# Circuit.net
KiCad netlist of a schematic drawn in EAGLE
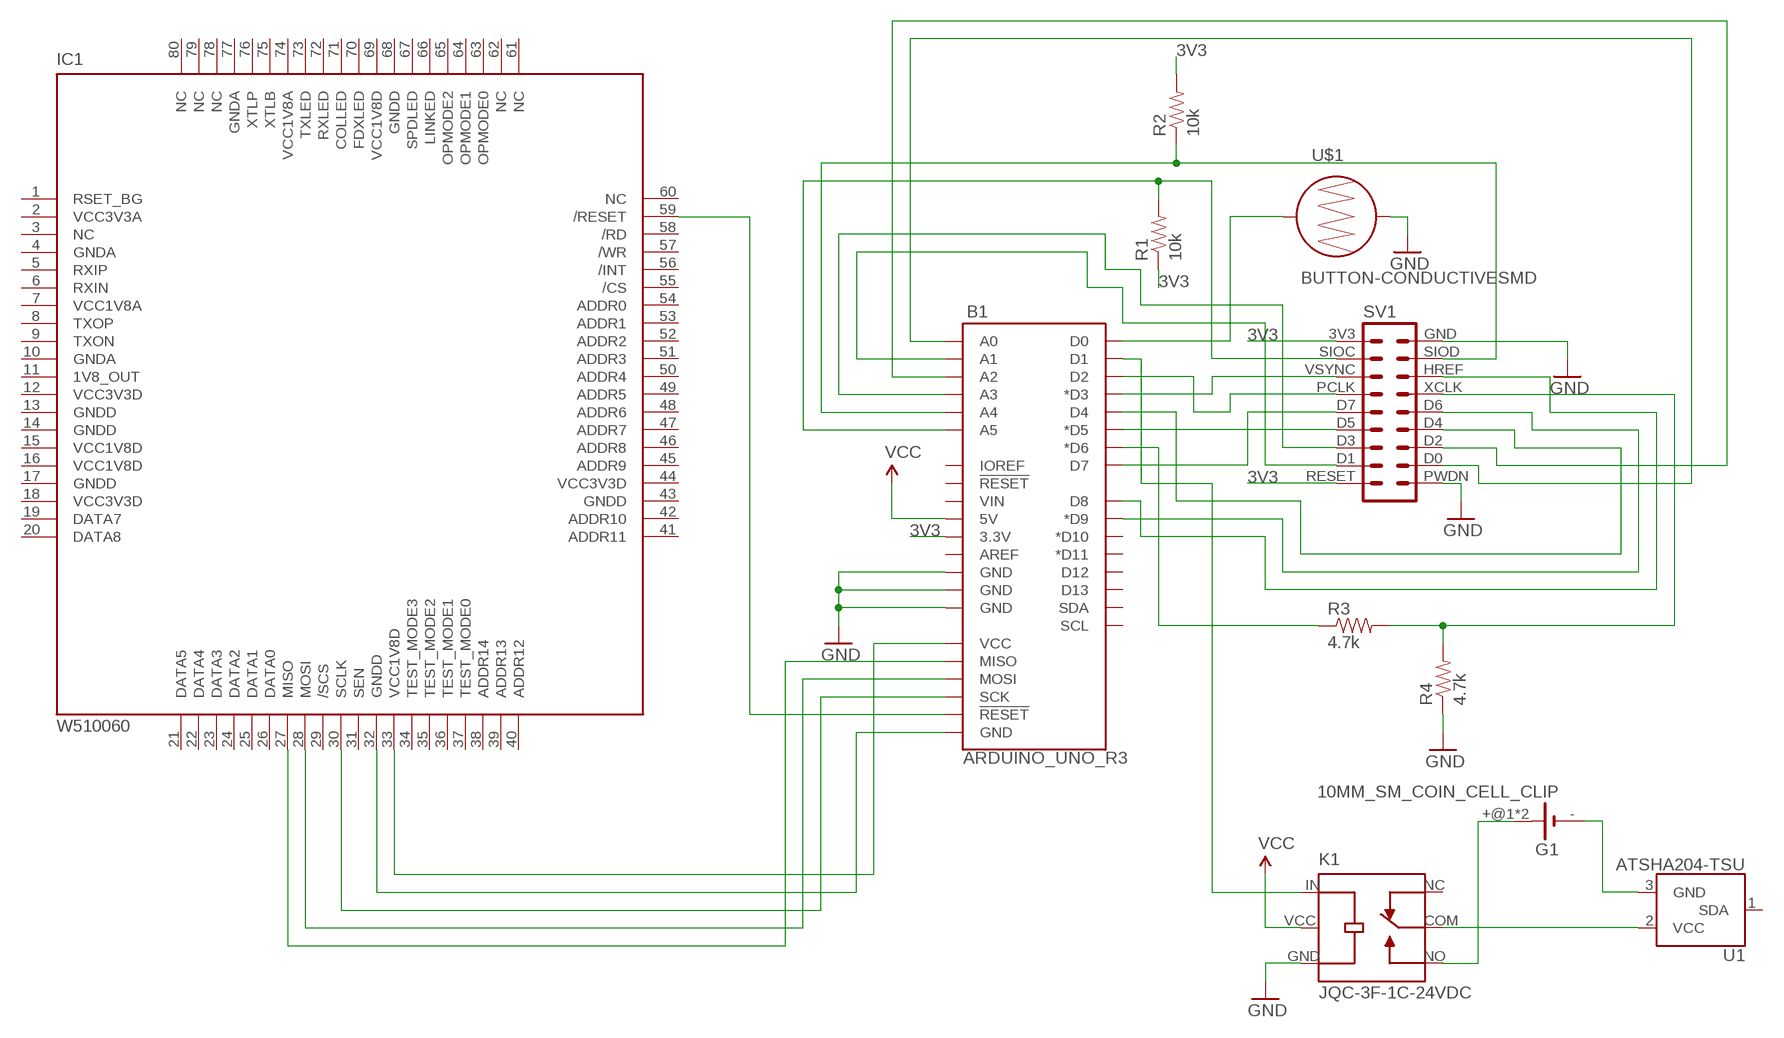
[diagram p0: schematic, sheet 1]

(export (version "E")
  (design (tool "Eeschema 10.0.6"))
  (components
    (comp (ref "B1")
      (value "ARDUINO_UNO_R3")
      (footprint "eagle-import:ARDUINO_R3")
      (libsource (lib "eagle-import") (part "ARDUINO_UNO_R3"))
    )
    (comp (ref "G1")
      (value "10MM_SM_COIN_CELL_CLIP")
      (footprint "eagle-import:10MM_SM_COIN_CELL_CLIP")
      (libsource (lib "eagle-import") (part "10MM_SM_COIN_CELL_CLIP"))
    )
    (comp (ref "IC1")
      (value "W510060")
      (footprint "eagle-import:W5100")
      (fields (field (name "MPN") "PIC18F86J60-I/PT"))
      (libsource (lib "eagle-import") (part "W510006"))
    )
    (comp (ref "K1")
      (value "JQC-3F-1C-24VDC")
      (footprint "eagle-import:RELAY_JQC-3F-1C-24VDC")
      (fields (field (name "MF") "YUEQING HENGWEI ELECTRONICS CO.,LTD."))
      (libsource (lib "eagle-import") (part "JQC-3F-1C-24VDC"))
    )
    (comp (ref "R1")
      (value "10k")
      (footprint "eagle-import:0402-RES")
      (libsource (lib "eagle-import") (part "RESISTOR0402"))
    )
    (comp (ref "R2")
      (value "10k")
      (footprint "eagle-import:0402-RES")
      (libsource (lib "eagle-import") (part "RESISTOR0402"))
    )
    (comp (ref "R3")
      (value "4.7k")
      (footprint "eagle-import:0402-RES")
      (libsource (lib "eagle-import") (part "RESISTOR0402"))
    )
    (comp (ref "R4")
      (value "4.7k")
      (footprint "eagle-import:0402-RES")
      (libsource (lib "eagle-import") (part "RESISTOR0402"))
    )
    (comp (ref "SV1")
      (value "ML16L")
      (footprint "eagle-import:ML16L")
      (libsource (lib "eagle-import") (part "ML16L"))
    )
    (comp (ref "U$1")
      (value "BUTTON-CONDUCTIVESMD")
      (footprint "eagle-import:BUTTON-CONDUCTIVE")
      (libsource (lib "eagle-import") (part "BUTTON-CONDUCTIVESMD"))
    )
    (comp (ref "U1")
      (value "ATSHA204-TSU")
      (footprint "eagle-import:SOT23-3")
      (libsource (lib "eagle-import") (part "ATSHA204-TSU"))
    )
  )
  (nets
    (net (code "1") (name "/1V8_OUT") (class "Default")
      (node (ref "IC1") (pin "11") (pinfunction "1V8_OUT_11") (pintype "power_in"))
    )
    (net (code "2") (name "/3V3") (class "Default")
      (node (ref "B1") (pin "3.3V") (pinfunction "3.3V_3.3V") (pintype "bidirectional"))
      (node (ref "R1") (pin "1") (pinfunction "1_1") (pintype "passive"))
      (node (ref "R2") (pin "2") (pinfunction "2_2") (pintype "passive"))
      (node (ref "SV1") (pin "3V3") (pinfunction "3V3_3V3") (pintype "passive"))
      (node (ref "SV1") (pin "RESET") (pinfunction "RESET_RESET") (pintype "passive"))
    )
    (net (code "3") (name "/ADDR3") (class "Default")
      (node (ref "IC1") (pin "51") (pinfunction "ADDR3_51") (pintype "power_in"))
    )
    (net (code "4") (name "/ADDR6") (class "Default")
      (node (ref "IC1") (pin "48") (pinfunction "ADDR6_48") (pintype "power_in"))
    )
    (net (code "5") (name "/COLLED") (class "Default")
      (node (ref "IC1") (pin "71") (pinfunction "COLLED_71") (pintype "power_in"))
    )
    (net (code "6") (name "/FDXLED") (class "Default")
      (node (ref "IC1") (pin "70") (pinfunction "FDXLED_70") (pintype "power_in"))
    )
    (net (code "7") (name "/SEN") (class "Default")
      (node (ref "IC1") (pin "31") (pinfunction "SEN_31") (pintype "power_in"))
    )
    (net (code "8") (name "GND") (class "Default")
      (node (ref "B1") (pin "GND@2") (pinfunction "GND_GND@2") (pintype "bidirectional"))
      (node (ref "B1") (pin "GND@3") (pinfunction "GND_GND@3") (pintype "bidirectional"))
      (node (ref "B1") (pin "GND@4") (pinfunction "GND_GND@4") (pintype "bidirectional"))
      (node (ref "K1") (pin "GND") (pinfunction "GND_GND") (pintype "passive"))
      (node (ref "R4") (pin "1") (pinfunction "1_1") (pintype "passive"))
      (node (ref "SV1") (pin "GND") (pinfunction "GND_GND") (pintype "passive"))
      (node (ref "SV1") (pin "PWDN") (pinfunction "PWDN_PWDN") (pintype "passive"))
      (node (ref "U$1") (pin "2") (pinfunction "2_2") (pintype "passive"))
    )
    (net (code "9") (name "Net-(B1-*D3)") (class "Default")
      (node (ref "B1") (pin "D3") (pinfunction "*D3_D3") (pintype "bidirectional"))
      (node (ref "SV1") (pin "VSYNC") (pinfunction "VSYNC_VSYNC") (pintype "passive"))
    )
    (net (code "10") (name "Net-(B1-*D5)") (class "Default")
      (node (ref "B1") (pin "D5") (pinfunction "*D5_D5") (pintype "bidirectional"))
      (node (ref "SV1") (pin "D5") (pinfunction "D5_D5") (pintype "passive"))
    )
    (net (code "11") (name "Net-(B1-*D6)") (class "Default")
      (node (ref "B1") (pin "D6") (pinfunction "*D6_D6") (pintype "bidirectional"))
      (node (ref "R3") (pin "1") (pinfunction "1_1") (pintype "passive"))
    )
    (net (code "12") (name "Net-(B1-*D9)") (class "Default")
      (node (ref "B1") (pin "D9") (pinfunction "*D9_D9") (pintype "bidirectional"))
      (node (ref "SV1") (pin "D6") (pinfunction "D6_D6") (pintype "passive"))
    )
    (net (code "13") (name "Net-(B1-GND-PadGND@1)") (class "Default")
      (node (ref "B1") (pin "GND@1") (pinfunction "GND_GND@1") (pintype "bidirectional"))
      (node (ref "IC1") (pin "32") (pinfunction "GNDD_32") (pintype "power_in"))
    )
    (net (code "14") (name "Net-(B1-PadA0)") (class "Default")
      (node (ref "B1") (pin "A0") (pinfunction "A0_A0") (pintype "bidirectional"))
      (node (ref "SV1") (pin "D0") (pinfunction "D0_D0") (pintype "passive"))
    )
    (net (code "15") (name "Net-(B1-PadA1)") (class "Default")
      (node (ref "B1") (pin "A1") (pinfunction "A1_A1") (pintype "bidirectional"))
      (node (ref "SV1") (pin "D1") (pinfunction "D1_D1") (pintype "passive"))
    )
    (net (code "16") (name "Net-(B1-PadA2)") (class "Default")
      (node (ref "B1") (pin "A2") (pinfunction "A2_A2") (pintype "bidirectional"))
      (node (ref "SV1") (pin "D2") (pinfunction "D2_D2") (pintype "passive"))
    )
    (net (code "17") (name "Net-(B1-PadA3)") (class "Default")
      (node (ref "B1") (pin "A3") (pinfunction "A3_A3") (pintype "bidirectional"))
      (node (ref "SV1") (pin "D3") (pinfunction "D3_D3") (pintype "passive"))
    )
    (net (code "18") (name "Net-(B1-PadA4)") (class "Default")
      (node (ref "B1") (pin "A4") (pinfunction "A4_A4") (pintype "bidirectional"))
      (node (ref "R2") (pin "1") (pinfunction "1_1") (pintype "passive"))
      (node (ref "SV1") (pin "SIOD") (pinfunction "SIOD_SIOD") (pintype "passive"))
    )
    (net (code "19") (name "Net-(B1-PadA5)") (class "Default")
      (node (ref "B1") (pin "A5") (pinfunction "A5_A5") (pintype "bidirectional"))
      (node (ref "R1") (pin "2") (pinfunction "2_2") (pintype "passive"))
      (node (ref "SV1") (pin "SIOC") (pinfunction "SIOC_SIOC") (pintype "passive"))
    )
    (net (code "20") (name "Net-(B1-PadD0)") (class "Default")
      (node (ref "B1") (pin "D0") (pinfunction "D0_D0") (pintype "bidirectional"))
      (node (ref "U$1") (pin "1") (pinfunction "1_1") (pintype "passive"))
    )
    (net (code "21") (name "Net-(B1-PadD1)") (class "Default")
      (node (ref "B1") (pin "D1") (pinfunction "D1_D1") (pintype "bidirectional"))
      (node (ref "K1") (pin "IN") (pinfunction "IN_IN") (pintype "passive"))
    )
    (net (code "22") (name "Net-(B1-PadD2)") (class "Default")
      (node (ref "B1") (pin "D2") (pinfunction "D2_D2") (pintype "bidirectional"))
      (node (ref "SV1") (pin "PCLK") (pinfunction "PCLK_PCLK") (pintype "passive"))
    )
    (net (code "23") (name "Net-(B1-PadD4)") (class "Default")
      (node (ref "B1") (pin "D4") (pinfunction "D4_D4") (pintype "bidirectional"))
      (node (ref "SV1") (pin "D4") (pinfunction "D4_D4") (pintype "passive"))
    )
    (net (code "24") (name "Net-(B1-PadD7)") (class "Default")
      (node (ref "B1") (pin "D7") (pinfunction "D7_D7") (pintype "bidirectional"))
      (node (ref "SV1") (pin "D7") (pinfunction "D7_D7") (pintype "passive"))
    )
    (net (code "25") (name "Net-(B1-PadD8)") (class "Default")
      (node (ref "B1") (pin "D8") (pinfunction "D8_D8") (pintype "bidirectional"))
      (node (ref "SV1") (pin "HREF") (pinfunction "HREF_HREF") (pintype "passive"))
    )
    (net (code "26") (name "Net-(B1-PadVCC)") (class "Default")
      (node (ref "B1") (pin "VCC") (pinfunction "VCC_VCC") (pintype "bidirectional"))
      (node (ref "IC1") (pin "33") (pinfunction "VCC1V8D_33") (pintype "bidirectional"))
    )
    (net (code "27") (name "Net-(G1-+-Pad+@1)") (class "Default")
      (node (ref "G1") (pin "+@1") (pinfunction "+_+@1") (pintype "passive"))
      (node (ref "G1") (pin "+@2") (pinfunction "+_+@2") (pintype "passive"))
      (node (ref "K1") (pin "NO") (pinfunction "NO_NO") (pintype "passive"))
    )
    (net (code "28") (name "Net-(IC1-MISO)") (class "Default")
      (node (ref "B1") (pin "MISO") (pinfunction "MISO_MISO") (pintype "bidirectional"))
      (node (ref "IC1") (pin "27") (pinfunction "MISO_27") (pintype "bidirectional"))
    )
    (net (code "29") (name "Net-(IC1-MOSI)") (class "Default")
      (node (ref "B1") (pin "MOSI") (pinfunction "MOSI_MOSI") (pintype "bidirectional"))
      (node (ref "IC1") (pin "28") (pinfunction "MOSI_28") (pintype "bidirectional"))
    )
    (net (code "30") (name "Net-(IC1-SCLK)") (class "Default")
      (node (ref "B1") (pin "SCK") (pinfunction "SCK_SCK") (pintype "bidirectional"))
      (node (ref "IC1") (pin "30") (pinfunction "SCLK_30") (pintype "bidirectional"))
    )
    (net (code "31") (name "Net-(IC1-{slash}RESET)") (class "Default")
      (node (ref "B1") (pin "RESET@2") (pinfunction "~{RESET}_RESET@2") (pintype "bidirectional"))
      (node (ref "IC1") (pin "59") (pinfunction "/RESET_59") (pintype "input"))
    )
    (net (code "32") (name "Net-(R3-Pad2)") (class "Default")
      (node (ref "R3") (pin "2") (pinfunction "2_2") (pintype "passive"))
      (node (ref "R4") (pin "2") (pinfunction "2_2") (pintype "passive"))
      (node (ref "SV1") (pin "XCLK") (pinfunction "XCLK_XCLK") (pintype "passive"))
    )
    (net (code "33") (name "Net-(U1-GND)") (class "Default")
      (node (ref "G1") (pin "-") (pinfunction "-_-") (pintype "passive"))
      (node (ref "U1") (pin "3") (pinfunction "GND_3") (pintype "bidirectional"))
    )
    (net (code "34") (name "Net-(U1-VCC)") (class "Default")
      (node (ref "K1") (pin "COM") (pinfunction "COM_COM") (pintype "passive"))
      (node (ref "U1") (pin "2") (pinfunction "VCC_2") (pintype "bidirectional"))
    )
    (net (code "35") (name "VCC") (class "Default")
      (node (ref "B1") (pin "5V") (pinfunction "5V_5V") (pintype "bidirectional"))
      (node (ref "K1") (pin "VCC") (pinfunction "VCC_VCC") (pintype "passive"))
    )
    (net (code "36") (name "unconnected-(B1-*D10-PadD10)") (class "Default")
      (node (ref "B1") (pin "D10") (pinfunction "*D10_D10") (pintype "bidirectional"))
    )
    (net (code "37") (name "unconnected-(B1-*D11-PadD11)") (class "Default")
      (node (ref "B1") (pin "D11") (pinfunction "*D11_D11") (pintype "bidirectional"))
    )
    (net (code "38") (name "unconnected-(B1-PadAREF)") (class "Default")
      (node (ref "B1") (pin "AREF") (pinfunction "AREF_AREF") (pintype "bidirectional"))
    )
    (net (code "39") (name "unconnected-(B1-PadD12)") (class "Default")
      (node (ref "B1") (pin "D12") (pinfunction "D12_D12") (pintype "bidirectional"))
    )
    (net (code "40") (name "unconnected-(B1-PadD13)") (class "Default")
      (node (ref "B1") (pin "D13") (pinfunction "D13_D13") (pintype "bidirectional"))
    )
    (net (code "41") (name "unconnected-(B1-PadIOREF)") (class "Default")
      (node (ref "B1") (pin "IOREF") (pinfunction "IOREF_IOREF") (pintype "bidirectional"))
    )
    (net (code "42") (name "unconnected-(B1-PadSCL)") (class "Default")
      (node (ref "B1") (pin "SCL") (pinfunction "SCL_SCL") (pintype "bidirectional"))
    )
    (net (code "43") (name "unconnected-(B1-PadSDA)") (class "Default")
      (node (ref "B1") (pin "SDA") (pinfunction "SDA_SDA") (pintype "bidirectional"))
    )
    (net (code "44") (name "unconnected-(B1-PadVIN)") (class "Default")
      (node (ref "B1") (pin "VIN") (pinfunction "VIN_VIN") (pintype "bidirectional"))
    )
    (net (code "45") (name "unconnected-(B1-~{RESET}-PadRESET@1)") (class "Default")
      (node (ref "B1") (pin "RESET@1") (pinfunction "~{RESET}_RESET@1") (pintype "bidirectional"))
    )
    (net (code "46") (name "unconnected-(IC1-ADDR0-Pad54)") (class "Default")
      (node (ref "IC1") (pin "54") (pinfunction "ADDR0_54") (pintype "bidirectional"))
    )
    (net (code "47") (name "unconnected-(IC1-ADDR1-Pad53)") (class "Default")
      (node (ref "IC1") (pin "53") (pinfunction "ADDR1_53") (pintype "bidirectional"))
    )
    (net (code "48") (name "unconnected-(IC1-ADDR2-Pad52)") (class "Default")
      (node (ref "IC1") (pin "52") (pinfunction "ADDR2_52") (pintype "bidirectional"))
    )
    (net (code "49") (name "unconnected-(IC1-ADDR4-Pad50)") (class "Default")
      (node (ref "IC1") (pin "50") (pinfunction "ADDR4_50") (pintype "output"))
    )
    (net (code "50") (name "unconnected-(IC1-ADDR5-Pad49)") (class "Default")
      (node (ref "IC1") (pin "49") (pinfunction "ADDR5_49") (pintype "input"))
    )
    (net (code "51") (name "unconnected-(IC1-ADDR7-Pad47)") (class "Default")
      (node (ref "IC1") (pin "47") (pinfunction "ADDR7_47") (pintype "bidirectional"))
    )
    (net (code "52") (name "unconnected-(IC1-ADDR8-Pad46)") (class "Default")
      (node (ref "IC1") (pin "46") (pinfunction "ADDR8_46") (pintype "bidirectional"))
    )
    (net (code "53") (name "unconnected-(IC1-ADDR9-Pad45)") (class "Default")
      (node (ref "IC1") (pin "45") (pinfunction "ADDR9_45") (pintype "bidirectional"))
    )
    (net (code "54") (name "unconnected-(IC1-ADDR10-Pad42)") (class "Default")
      (node (ref "IC1") (pin "42") (pinfunction "ADDR10_42") (pintype "bidirectional"))
    )
    (net (code "55") (name "unconnected-(IC1-ADDR11-Pad41)") (class "Default")
      (node (ref "IC1") (pin "41") (pinfunction "ADDR11_41") (pintype "bidirectional"))
    )
    (net (code "56") (name "unconnected-(IC1-ADDR12-Pad40)") (class "Default")
      (node (ref "IC1") (pin "40") (pinfunction "ADDR12_40") (pintype "bidirectional"))
    )
    (net (code "57") (name "unconnected-(IC1-ADDR13-Pad39)") (class "Default")
      (node (ref "IC1") (pin "39") (pinfunction "ADDR13_39") (pintype "bidirectional"))
    )
    (net (code "58") (name "unconnected-(IC1-ADDR14-Pad38)") (class "Default")
      (node (ref "IC1") (pin "38") (pinfunction "ADDR14_38") (pintype "bidirectional"))
    )
    (net (code "59") (name "unconnected-(IC1-DATA0-Pad26)") (class "Default")
      (node (ref "IC1") (pin "26") (pinfunction "DATA0_26") (pintype "input"))
    )
    (net (code "60") (name "unconnected-(IC1-DATA1-Pad25)") (class "Default")
      (node (ref "IC1") (pin "25") (pinfunction "DATA1_25") (pintype "input"))
    )
    (net (code "61") (name "unconnected-(IC1-DATA2-Pad24)") (class "Default")
      (node (ref "IC1") (pin "24") (pinfunction "DATA2_24") (pintype "input"))
    )
    (net (code "62") (name "unconnected-(IC1-DATA3-Pad23)") (class "Default")
      (node (ref "IC1") (pin "23") (pinfunction "DATA3_23") (pintype "bidirectional"))
    )
    (net (code "63") (name "unconnected-(IC1-DATA4-Pad22)") (class "Default")
      (node (ref "IC1") (pin "22") (pinfunction "DATA4_22") (pintype "bidirectional"))
    )
    (net (code "64") (name "unconnected-(IC1-DATA5-Pad21)") (class "Default")
      (node (ref "IC1") (pin "21") (pinfunction "DATA5_21") (pintype "bidirectional"))
    )
    (net (code "65") (name "unconnected-(IC1-DATA7-Pad19)") (class "Default")
      (node (ref "IC1") (pin "19") (pinfunction "DATA7_19") (pintype "bidirectional"))
    )
    (net (code "66") (name "unconnected-(IC1-DATA8-Pad20)") (class "Default")
      (node (ref "IC1") (pin "20") (pinfunction "DATA8_20") (pintype "bidirectional"))
    )
    (net (code "67") (name "unconnected-(IC1-GNDA-Pad4)") (class "Default")
      (node (ref "IC1") (pin "4") (pinfunction "GNDA_4") (pintype "bidirectional"))
    )
    (net (code "68") (name "unconnected-(IC1-GNDA-Pad10)") (class "Default")
      (node (ref "IC1") (pin "10") (pinfunction "GNDA_10") (pintype "bidirectional"))
    )
    (net (code "69") (name "unconnected-(IC1-GNDA-Pad77)") (class "Default")
      (node (ref "IC1") (pin "77") (pinfunction "GNDA_77") (pintype "bidirectional"))
    )
    (net (code "70") (name "unconnected-(IC1-GNDD-Pad13)") (class "Default")
      (node (ref "IC1") (pin "13") (pinfunction "GNDD_13") (pintype "bidirectional"))
    )
    (net (code "71") (name "unconnected-(IC1-GNDD-Pad14)") (class "Default")
      (node (ref "IC1") (pin "14") (pinfunction "GNDD_14") (pintype "bidirectional"))
    )
    (net (code "72") (name "unconnected-(IC1-GNDD-Pad17)") (class "Default")
      (node (ref "IC1") (pin "17") (pinfunction "GNDD_17") (pintype "bidirectional"))
    )
    (net (code "73") (name "unconnected-(IC1-GNDD-Pad43)") (class "Default")
      (node (ref "IC1") (pin "43") (pinfunction "GNDD_43") (pintype "bidirectional"))
    )
    (net (code "74") (name "unconnected-(IC1-GNDD-Pad68)") (class "Default")
      (node (ref "IC1") (pin "68") (pinfunction "GNDD_68") (pintype "bidirectional"))
    )
    (net (code "75") (name "unconnected-(IC1-LINKED-Pad66)") (class "Default")
      (node (ref "IC1") (pin "66") (pinfunction "LINKED_66") (pintype "input"))
    )
    (net (code "76") (name "unconnected-(IC1-NC-Pad3)") (class "Default")
      (node (ref "IC1") (pin "3") (pinfunction "NC_3") (pintype "bidirectional"))
    )
    (net (code "77") (name "unconnected-(IC1-NC-Pad60)") (class "Default")
      (node (ref "IC1") (pin "60") (pinfunction "NC_60") (pintype "input"))
    )
    (net (code "78") (name "unconnected-(IC1-NC-Pad61)") (class "Default")
      (node (ref "IC1") (pin "61") (pinfunction "NC_61") (pintype "input"))
    )
    (net (code "79") (name "unconnected-(IC1-NC-Pad62)") (class "Default")
      (node (ref "IC1") (pin "62") (pinfunction "NC_62") (pintype "output"))
    )
    (net (code "80") (name "unconnected-(IC1-NC-Pad78)") (class "Default")
      (node (ref "IC1") (pin "78") (pinfunction "NC_78") (pintype "bidirectional"))
    )
    (net (code "81") (name "unconnected-(IC1-NC-Pad79)") (class "Default")
      (node (ref "IC1") (pin "79") (pinfunction "NC_79") (pintype "bidirectional"))
    )
    (net (code "82") (name "unconnected-(IC1-NC-Pad80)") (class "Default")
      (node (ref "IC1") (pin "80") (pinfunction "NC_80") (pintype "bidirectional"))
    )
    (net (code "83") (name "unconnected-(IC1-OPMODE0-Pad63)") (class "Default")
      (node (ref "IC1") (pin "63") (pinfunction "OPMODE0_63") (pintype "output"))
    )
    (net (code "84") (name "unconnected-(IC1-OPMODE1-Pad64)") (class "Default")
      (node (ref "IC1") (pin "64") (pinfunction "OPMODE1_64") (pintype "input"))
    )
    (net (code "85") (name "unconnected-(IC1-OPMODE2-Pad65)") (class "Default")
      (node (ref "IC1") (pin "65") (pinfunction "OPMODE2_65") (pintype "input"))
    )
    (net (code "86") (name "unconnected-(IC1-RSET_BG-Pad1)") (class "Default")
      (node (ref "IC1") (pin "1") (pinfunction "RSET_BG_1") (pintype "bidirectional"))
    )
    (net (code "87") (name "unconnected-(IC1-RXIN-Pad6)") (class "Default")
      (node (ref "IC1") (pin "6") (pinfunction "RXIN_6") (pintype "bidirectional"))
    )
    (net (code "88") (name "unconnected-(IC1-RXIP-Pad5)") (class "Default")
      (node (ref "IC1") (pin "5") (pinfunction "RXIP_5") (pintype "bidirectional"))
    )
    (net (code "89") (name "unconnected-(IC1-RXLED-Pad72)") (class "Default")
      (node (ref "IC1") (pin "72") (pinfunction "RXLED_72") (pintype "bidirectional"))
    )
    (net (code "90") (name "unconnected-(IC1-SPDLED-Pad67)") (class "Default")
      (node (ref "IC1") (pin "67") (pinfunction "SPDLED_67") (pintype "input"))
    )
    (net (code "91") (name "unconnected-(IC1-TEST_MODE0-Pad37)") (class "Default")
      (node (ref "IC1") (pin "37") (pinfunction "TEST_MODE0_37") (pintype "bidirectional"))
    )
    (net (code "92") (name "unconnected-(IC1-TEST_MODE1-Pad36)") (class "Default")
      (node (ref "IC1") (pin "36") (pinfunction "TEST_MODE1_36") (pintype "bidirectional"))
    )
    (net (code "93") (name "unconnected-(IC1-TEST_MODE2-Pad35)") (class "Default")
      (node (ref "IC1") (pin "35") (pinfunction "TEST_MODE2_35") (pintype "bidirectional"))
    )
    (net (code "94") (name "unconnected-(IC1-TEST_MODE3-Pad34)") (class "Default")
      (node (ref "IC1") (pin "34") (pinfunction "TEST_MODE3_34") (pintype "bidirectional"))
    )
    (net (code "95") (name "unconnected-(IC1-TXLED-Pad73)") (class "Default")
      (node (ref "IC1") (pin "73") (pinfunction "TXLED_73") (pintype "bidirectional"))
    )
    (net (code "96") (name "unconnected-(IC1-TXON-Pad9)") (class "Default")
      (node (ref "IC1") (pin "9") (pinfunction "TXON_9") (pintype "input"))
    )
    (net (code "97") (name "unconnected-(IC1-TXOP-Pad8)") (class "Default")
      (node (ref "IC1") (pin "8") (pinfunction "TXOP_8") (pintype "bidirectional"))
    )
    (net (code "98") (name "unconnected-(IC1-VCC1V8A-Pad7)") (class "Default")
      (node (ref "IC1") (pin "7") (pinfunction "VCC1V8A_7") (pintype "bidirectional"))
    )
    (net (code "99") (name "unconnected-(IC1-VCC1V8A-Pad74)") (class "Default")
      (node (ref "IC1") (pin "74") (pinfunction "VCC1V8A_74") (pintype "bidirectional"))
    )
    (net (code "100") (name "unconnected-(IC1-VCC1V8D-Pad15)") (class "Default")
      (node (ref "IC1") (pin "15") (pinfunction "VCC1V8D_15") (pintype "bidirectional"))
    )
    (net (code "101") (name "unconnected-(IC1-VCC1V8D-Pad16)") (class "Default")
      (node (ref "IC1") (pin "16") (pinfunction "VCC1V8D_16") (pintype "bidirectional"))
    )
    (net (code "102") (name "unconnected-(IC1-VCC1V8D-Pad69)") (class "Default")
      (node (ref "IC1") (pin "69") (pinfunction "VCC1V8D_69") (pintype "bidirectional"))
    )
    (net (code "103") (name "unconnected-(IC1-VCC3V3A-Pad2)") (class "Default")
      (node (ref "IC1") (pin "2") (pinfunction "VCC3V3A_2") (pintype "bidirectional"))
    )
    (net (code "104") (name "unconnected-(IC1-VCC3V3D-Pad12)") (class "Default")
      (node (ref "IC1") (pin "12") (pinfunction "VCC3V3D_12") (pintype "input"))
    )
    (net (code "105") (name "unconnected-(IC1-VCC3V3D-Pad18)") (class "Default")
      (node (ref "IC1") (pin "18") (pinfunction "VCC3V3D_18") (pintype "bidirectional"))
    )
    (net (code "106") (name "unconnected-(IC1-VCC3V3D-Pad44)") (class "Default")
      (node (ref "IC1") (pin "44") (pinfunction "VCC3V3D_44") (pintype "bidirectional"))
    )
    (net (code "107") (name "unconnected-(IC1-XTLB-Pad75)") (class "Default")
      (node (ref "IC1") (pin "75") (pinfunction "XTLB_75") (pintype "bidirectional"))
    )
    (net (code "108") (name "unconnected-(IC1-XTLP-Pad76)") (class "Default")
      (node (ref "IC1") (pin "76") (pinfunction "XTLP_76") (pintype "bidirectional"))
    )
    (net (code "109") (name "unconnected-(IC1-{slash}CS-Pad55)") (class "Default")
      (node (ref "IC1") (pin "55") (pinfunction "/CS_55") (pintype "bidirectional"))
    )
    (net (code "110") (name "unconnected-(IC1-{slash}INT-Pad56)") (class "Default")
      (node (ref "IC1") (pin "56") (pinfunction "/INT_56") (pintype "bidirectional"))
    )
    (net (code "111") (name "unconnected-(IC1-{slash}RD-Pad58)") (class "Default")
      (node (ref "IC1") (pin "58") (pinfunction "/RD_58") (pintype "input"))
    )
    (net (code "112") (name "unconnected-(IC1-{slash}SCS-Pad29)") (class "Default")
      (node (ref "IC1") (pin "29") (pinfunction "/SCS_29") (pintype "bidirectional"))
    )
    (net (code "113") (name "unconnected-(IC1-{slash}WR-Pad57)") (class "Default")
      (node (ref "IC1") (pin "57") (pinfunction "/WR_57") (pintype "input"))
    )
    (net (code "114") (name "unconnected-(K1-PadNC)") (class "Default")
      (node (ref "K1") (pin "NC") (pinfunction "NC_NC") (pintype "passive"))
    )
    (net (code "115") (name "unconnected-(U1-SDA-Pad1)") (class "Default")
      (node (ref "U1") (pin "1") (pinfunction "SDA_1") (pintype "bidirectional"))
    )
  )
)
